# adapterSchematic.net
KiCad netlist of a schematic drawn in EAGLE
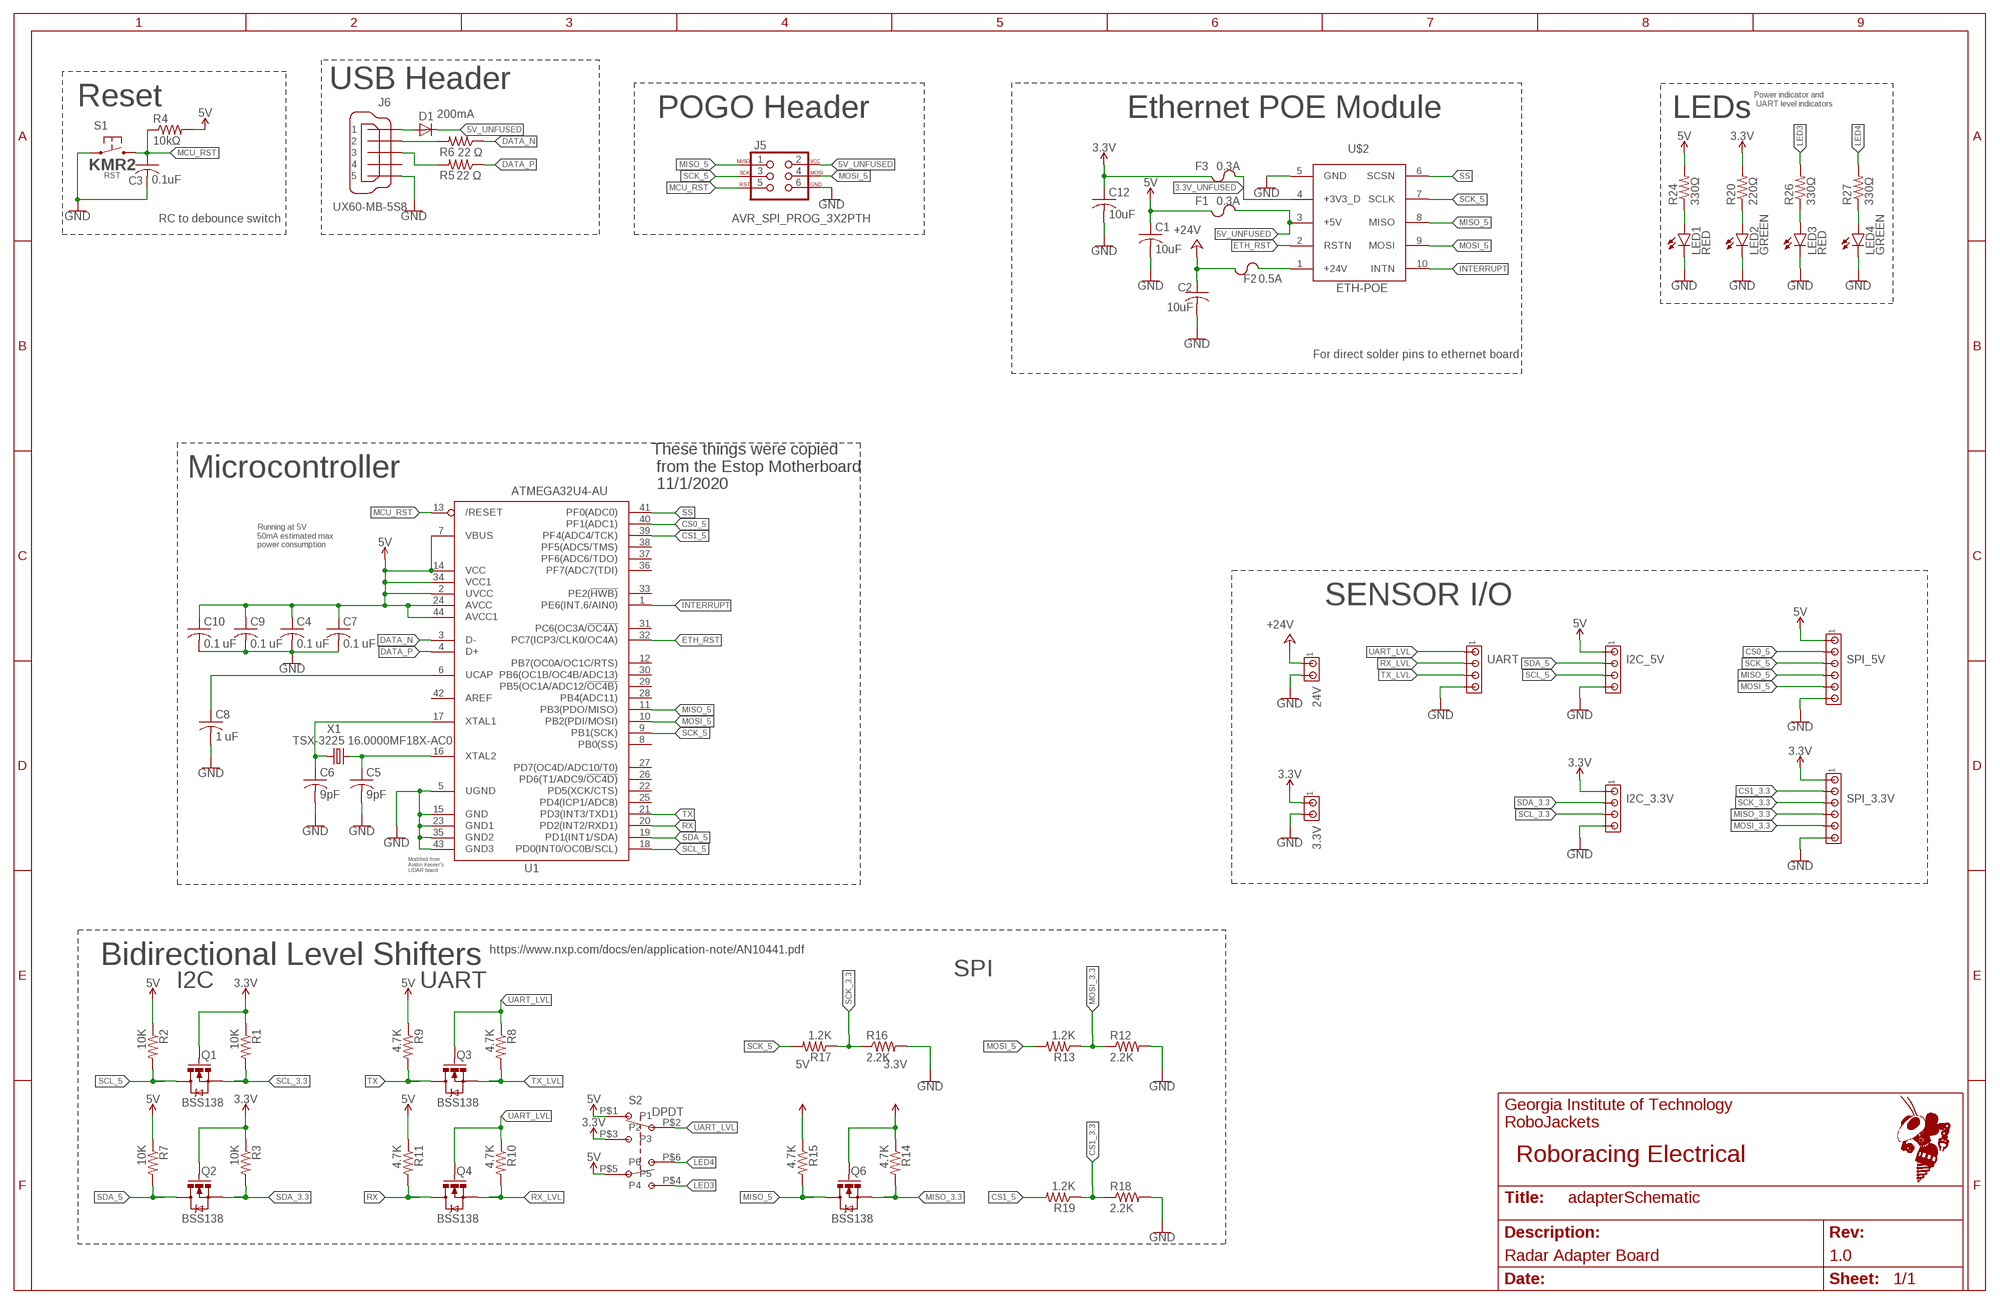
[diagram p0: schematic, sheet 1]

(export (version "E")
  (design (tool "Eeschema 10.0.6"))
  (components
    (comp (ref "3.3V")
      (value "MTA02-100")
      (footprint "eagle-import:10X02MTA")
      (libsource (lib "eagle-import") (part "MTA02-100"))
    )
    (comp (ref "24V")
      (value "MTA02-100")
      (footprint "eagle-import:10X02MTA")
      (libsource (lib "eagle-import") (part "MTA02-100"))
    )
    (comp (ref "C1")
      (value "10uF")
      (footprint "eagle-import:C1206")
      (libsource (lib "eagle-import") (part "C-USC1206"))
    )
    (comp (ref "C2")
      (value "10uF")
      (footprint "eagle-import:C1206")
      (libsource (lib "eagle-import") (part "C-USC1206"))
    )
    (comp (ref "C3")
      (value "0.1uF")
      (footprint "eagle-import:C0603")
      (libsource (lib "eagle-import") (part "C-USC0603"))
    )
    (comp (ref "C4")
      (value "0.1 uF")
      (footprint "eagle-import:C0603")
      (libsource (lib "eagle-import") (part "resistor_348_C-USC0603"))
    )
    (comp (ref "C5")
      (value "9pF")
      (footprint "eagle-import:C0603")
      (libsource (lib "eagle-import") (part "resistor_348_C-USC0603"))
    )
    (comp (ref "C6")
      (value "9pF")
      (footprint "eagle-import:C0603")
      (libsource (lib "eagle-import") (part "resistor_348_C-USC0603"))
    )
    (comp (ref "C7")
      (value "0.1 uF")
      (footprint "eagle-import:C0603")
      (libsource (lib "eagle-import") (part "resistor_348_C-USC0603"))
    )
    (comp (ref "C8")
      (value "1 uF")
      (footprint "eagle-import:C0603")
      (libsource (lib "eagle-import") (part "resistor_348_C-USC0603"))
    )
    (comp (ref "C9")
      (value "0.1 uF")
      (footprint "eagle-import:C0603")
      (libsource (lib "eagle-import") (part "resistor_348_C-USC0603"))
    )
    (comp (ref "C10")
      (value "0.1 uF")
      (footprint "eagle-import:C0603")
      (libsource (lib "eagle-import") (part "resistor_348_C-USC0603"))
    )
    (comp (ref "C12")
      (value "10uF")
      (footprint "eagle-import:C1206")
      (libsource (lib "eagle-import") (part "C-USC1206"))
    )
    (comp (ref "D1")
      (value "200mA")
      (footprint "eagle-import:SOD323-R")
      (libsource (lib "eagle-import") (part "DIODE-SOD323-R"))
    )
    (comp (ref "F1")
      (value "0.3A")
      (footprint "eagle-import:F1206")
      (libsource (lib "eagle-import") (part "CHIP_FUSE1206"))
    )
    (comp (ref "F2")
      (value "0.5A")
      (footprint "eagle-import:F1206")
      (libsource (lib "eagle-import") (part "CHIP_FUSE1206"))
    )
    (comp (ref "F3")
      (value "0.3A")
      (footprint "eagle-import:F1206")
      (libsource (lib "eagle-import") (part "CHIP_FUSE1206"))
    )
    (comp (ref "I2C_3.3V")
      (value "MTA04-100")
      (footprint "eagle-import:10X04MTA")
      (libsource (lib "eagle-import") (part "MTA04-100"))
    )
    (comp (ref "I2C_5V")
      (value "MTA04-100")
      (footprint "eagle-import:10X04MTA")
      (libsource (lib "eagle-import") (part "MTA04-100"))
    )
    (comp (ref "J5")
      (value "AVR_SPI_PROG_3X2PTH")
      (footprint "eagle-import:2X3")
      (libsource (lib "eagle-import") (part "AVR_SPI_PROG_3X2PTH"))
    )
    (comp (ref "J6")
      (value "UX60-MB-5S8")
      (footprint "eagle-import:UX60-MB-5S8")
      (libsource (lib "eagle-import") (part "UX60-MB-5S?8"))
    )
    (comp (ref "LED1")
      (value "RED")
      (footprint "eagle-import:CHIP-LED0603")
      (libsource (lib "eagle-import") (part "LEDCHIP-LED0603"))
    )
    (comp (ref "LED2")
      (value "GREEN")
      (footprint "eagle-import:CHIP-LED0603")
      (libsource (lib "eagle-import") (part "LEDCHIP-LED0603"))
    )
    (comp (ref "LED3")
      (value "RED")
      (footprint "eagle-import:CHIP-LED0603")
      (libsource (lib "eagle-import") (part "LEDCHIP-LED0603"))
    )
    (comp (ref "LED4")
      (value "GREEN")
      (footprint "eagle-import:CHIP-LED0603")
      (libsource (lib "eagle-import") (part "LEDCHIP-LED0603"))
    )
    (comp (ref "Q1")
      (value "BSS138")
      (footprint "eagle-import:SOT23-3")
      (libsource (lib "eagle-import") (part "MOSFET-NCHANNELSMD"))
    )
    (comp (ref "Q2")
      (value "BSS138")
      (footprint "eagle-import:SOT23-3")
      (libsource (lib "eagle-import") (part "MOSFET-NCHANNELSMD"))
    )
    (comp (ref "Q3")
      (value "BSS138")
      (footprint "eagle-import:SOT23-3")
      (libsource (lib "eagle-import") (part "MOSFET-NCHANNELSMD"))
    )
    (comp (ref "Q4")
      (value "BSS138")
      (footprint "eagle-import:SOT23-3")
      (libsource (lib "eagle-import") (part "MOSFET-NCHANNELSMD"))
    )
    (comp (ref "Q6")
      (value "BSS138")
      (footprint "eagle-import:SOT23-3")
      (libsource (lib "eagle-import") (part "MOSFET-NCHANNELSMD"))
    )
    (comp (ref "R1")
      (value "10K")
      (footprint "eagle-import:0603-RES")
      (libsource (lib "eagle-import") (part "RESISTOR0603-RES"))
    )
    (comp (ref "R2")
      (value "10K")
      (footprint "eagle-import:0603-RES")
      (libsource (lib "eagle-import") (part "RESISTOR0603-RES"))
    )
    (comp (ref "R3")
      (value "10K")
      (footprint "eagle-import:0603-RES")
      (libsource (lib "eagle-import") (part "RESISTOR0603-RES"))
    )
    (comp (ref "R4")
      (value "10kΩ")
      (footprint "eagle-import:R0603")
      (libsource (lib "eagle-import") (part "R-US_R0603"))
    )
    (comp (ref "R5")
      (value "22 Ω")
      (footprint "eagle-import:R0603")
      (libsource (lib "eagle-import") (part "R-US_R0603"))
    )
    (comp (ref "R6")
      (value "22 Ω")
      (footprint "eagle-import:R0603")
      (libsource (lib "eagle-import") (part "R-US_R0603"))
    )
    (comp (ref "R7")
      (value "10K")
      (footprint "eagle-import:0603-RES")
      (libsource (lib "eagle-import") (part "RESISTOR0603-RES"))
    )
    (comp (ref "R8")
      (value "4.7K")
      (footprint "eagle-import:0603-RES")
      (libsource (lib "eagle-import") (part "RESISTOR0603-RES"))
    )
    (comp (ref "R9")
      (value "4.7K")
      (footprint "eagle-import:0603-RES")
      (libsource (lib "eagle-import") (part "RESISTOR0603-RES"))
    )
    (comp (ref "R10")
      (value "4.7K")
      (footprint "eagle-import:0603-RES")
      (libsource (lib "eagle-import") (part "RESISTOR0603-RES"))
    )
    (comp (ref "R11")
      (value "4.7K")
      (footprint "eagle-import:0603-RES")
      (libsource (lib "eagle-import") (part "RESISTOR0603-RES"))
    )
    (comp (ref "R12")
      (value "2.2K")
      (footprint "eagle-import:0603-RES")
      (libsource (lib "eagle-import") (part "RESISTOR0603-RES"))
    )
    (comp (ref "R13")
      (value "1.2K")
      (footprint "eagle-import:0603-RES")
      (libsource (lib "eagle-import") (part "RESISTOR0603-RES"))
    )
    (comp (ref "R14")
      (value "4.7K")
      (footprint "eagle-import:0603-RES")
      (libsource (lib "eagle-import") (part "RESISTOR0603-RES"))
    )
    (comp (ref "R15")
      (value "4.7K")
      (footprint "eagle-import:0603-RES")
      (libsource (lib "eagle-import") (part "RESISTOR0603-RES"))
    )
    (comp (ref "R16")
      (value "2.2K")
      (footprint "eagle-import:0603-RES")
      (libsource (lib "eagle-import") (part "RESISTOR0603-RES"))
    )
    (comp (ref "R17")
      (value "1.2K")
      (footprint "eagle-import:0603-RES")
      (libsource (lib "eagle-import") (part "RESISTOR0603-RES"))
    )
    (comp (ref "R18")
      (value "2.2K")
      (footprint "eagle-import:0603-RES")
      (libsource (lib "eagle-import") (part "RESISTOR0603-RES"))
    )
    (comp (ref "R19")
      (value "1.2K")
      (footprint "eagle-import:0603-RES")
      (libsource (lib "eagle-import") (part "RESISTOR0603-RES"))
    )
    (comp (ref "R20")
      (value "220Ω")
      (footprint "eagle-import:R0603")
      (libsource (lib "eagle-import") (part "R-US_R0603"))
    )
    (comp (ref "R24")
      (value "330Ω")
      (footprint "eagle-import:R0603")
      (libsource (lib "eagle-import") (part "R-US_R0603"))
    )
    (comp (ref "R26")
      (value "330Ω")
      (footprint "eagle-import:R0603")
      (libsource (lib "eagle-import") (part "R-US_R0603"))
    )
    (comp (ref "R27")
      (value "330Ω")
      (footprint "eagle-import:R0603")
      (libsource (lib "eagle-import") (part "R-US_R0603"))
    )
    (comp (ref "S1")
      (value "KMR2")
      (footprint "eagle-import:KMR2")
      (fields (field (name "FUNCTION") "Reset") (field (name "FUNCTION_1") "RST"))
      (libsource (lib "eagle-import") (part "KMR2"))
    )
    (comp (ref "SPI_3.3V")
      (value "MTA06-100")
      (footprint "eagle-import:10X06MTA")
      (libsource (lib "eagle-import") (part "MTA06-100"))
    )
    (comp (ref "SPI_5V")
      (value "MTA06-100")
      (footprint "eagle-import:10X06MTA")
      (libsource (lib "eagle-import") (part "MTA06-100"))
    )
    (comp (ref "U$2")
      (value "ETH-POE")
      (footprint "eagle-import:HDRVR10W64P4000X254_2X5_1016X508X254B")
      (libsource (lib "eagle-import") (part "ETH-POE"))
    )
    (comp (ref "U$4")
      (value "DPDT_SLIDE_SWITCH")
      (footprint "eagle-import:DPDT_SLIDE_SWITCH")
      (libsource (lib "eagle-import") (part "DPDT_SLIDE_SWITCH"))
    )
    (comp (ref "U1")
      (value "ATMEGA32U4-AU")
      (footprint "eagle-import:TQFP44")
      (libsource (lib "eagle-import") (part "ATMEGA32U4-AU"))
    )
    (comp (ref "UART")
      (value "MTA04-100")
      (footprint "eagle-import:10X04MTA")
      (libsource (lib "eagle-import") (part "MTA04-100"))
    )
    (comp (ref "X1")
      (value "TSX-3225 16.0000MF18X-AC0")
      (footprint "eagle-import:XTAL-3.2X2.5")
      (libsource (lib "eagle-import") (part "XTAL-3.2X2.5"))
    )
  )
  (nets
    (net (code "1") (name "+24V") (class "Default")
      (node (ref "24V") (pin "1") (pinfunction "1_1") (pintype "passive"))
      (node (ref "C2") (pin "1") (pinfunction "1_1") (pintype "passive"))
      (node (ref "F2") (pin "1") (pinfunction "1_1") (pintype "bidirectional"))
    )
    (net (code "2") (name "3.3V") (class "Default")
      (node (ref "3.3V") (pin "1") (pinfunction "1_1") (pintype "passive"))
      (node (ref "C12") (pin "1") (pinfunction "1_1") (pintype "passive"))
      (node (ref "F3") (pin "1") (pinfunction "1_1") (pintype "bidirectional"))
      (node (ref "I2C_3.3V") (pin "1") (pinfunction "1_1") (pintype "passive"))
      (node (ref "Q1") (pin "1") (pinfunction "G_1") (pintype "passive"))
      (node (ref "Q2") (pin "1") (pinfunction "G_1") (pintype "passive"))
      (node (ref "Q6") (pin "1") (pinfunction "G_1") (pintype "passive"))
      (node (ref "R1") (pin "1") (pinfunction "1_1") (pintype "passive"))
      (node (ref "R14") (pin "1") (pinfunction "1_1") (pintype "passive"))
      (node (ref "R20") (pin "2") (pinfunction "2_2") (pintype "passive"))
      (node (ref "R3") (pin "1") (pinfunction "1_1") (pintype "passive"))
      (node (ref "SPI_3.3V") (pin "1") (pinfunction "1_1") (pintype "passive"))
      (node (ref "U$4") (pin "P$3") (pinfunction "P3_P$3") (pintype "bidirectional"))
    )
    (net (code "3") (name "3.3V_UNFUSED") (class "Default")
      (node (ref "F3") (pin "2") (pinfunction "2_2") (pintype "bidirectional"))
      (node (ref "U$2") (pin "4") (pinfunction "+3V3_D_4") (pintype "bidirectional"))
    )
    (net (code "4") (name "5V") (class "Default")
      (node (ref "C1") (pin "1") (pinfunction "1_1") (pintype "passive"))
      (node (ref "C10") (pin "1") (pinfunction "1_1") (pintype "passive"))
      (node (ref "C4") (pin "1") (pinfunction "1_1") (pintype "passive"))
      (node (ref "C7") (pin "1") (pinfunction "1_1") (pintype "passive"))
      (node (ref "C9") (pin "1") (pinfunction "1_1") (pintype "passive"))
      (node (ref "F1") (pin "1") (pinfunction "1_1") (pintype "bidirectional"))
      (node (ref "I2C_5V") (pin "1") (pinfunction "1_1") (pintype "passive"))
      (node (ref "R11") (pin "1") (pinfunction "1_1") (pintype "passive"))
      (node (ref "R15") (pin "1") (pinfunction "1_1") (pintype "passive"))
      (node (ref "R2") (pin "1") (pinfunction "1_1") (pintype "passive"))
      (node (ref "R24") (pin "2") (pinfunction "2_2") (pintype "passive"))
      (node (ref "R4") (pin "2") (pinfunction "2_2") (pintype "passive"))
      (node (ref "R7") (pin "1") (pinfunction "1_1") (pintype "passive"))
      (node (ref "R9") (pin "1") (pinfunction "1_1") (pintype "passive"))
      (node (ref "SPI_5V") (pin "1") (pinfunction "1_1") (pintype "passive"))
      (node (ref "U$4") (pin "P$1") (pinfunction "P1_P$1") (pintype "bidirectional"))
      (node (ref "U$4") (pin "P$5") (pinfunction "P5_P$5") (pintype "bidirectional"))
      (node (ref "U1") (pin "14") (pinfunction "VCC_14") (pintype "bidirectional"))
      (node (ref "U1") (pin "2") (pinfunction "UVCC_2") (pintype "bidirectional"))
      (node (ref "U1") (pin "24") (pinfunction "AVCC_24") (pintype "bidirectional"))
      (node (ref "U1") (pin "34") (pinfunction "VCC1_34") (pintype "bidirectional"))
      (node (ref "U1") (pin "44") (pinfunction "AVCC1_44") (pintype "bidirectional"))
      (node (ref "U1") (pin "7") (pinfunction "VBUS_7") (pintype "bidirectional"))
    )
    (net (code "5") (name "5V_UNFUSED") (class "Default")
      (node (ref "D1") (pin "C") (pinfunction "C_C") (pintype "passive"))
      (node (ref "F1") (pin "2") (pinfunction "2_2") (pintype "bidirectional"))
      (node (ref "J5") (pin "2") (pinfunction "2_2") (pintype "passive"))
      (node (ref "U$2") (pin "3") (pinfunction "+5V_3") (pintype "bidirectional"))
    )
    (net (code "6") (name "CS0_5") (class "Default")
      (node (ref "SPI_5V") (pin "2") (pinfunction "2_2") (pintype "passive"))
      (node (ref "U1") (pin "40") (pinfunction "PF1(ADC1)_40") (pintype "bidirectional"))
    )
    (net (code "7") (name "CS1_3.3") (class "Default")
      (node (ref "R18") (pin "1") (pinfunction "1_1") (pintype "passive"))
      (node (ref "R19") (pin "1") (pinfunction "1_1") (pintype "passive"))
      (node (ref "SPI_3.3V") (pin "2") (pinfunction "2_2") (pintype "passive"))
    )
    (net (code "8") (name "CS1_5") (class "Default")
      (node (ref "R19") (pin "2") (pinfunction "2_2") (pintype "passive"))
      (node (ref "U1") (pin "39") (pinfunction "PF4(ADC4/TCK)_39") (pintype "bidirectional"))
    )
    (net (code "9") (name "DATA_N") (class "Default")
      (node (ref "R6") (pin "1") (pinfunction "1_1") (pintype "passive"))
      (node (ref "U1") (pin "3") (pinfunction "D-_3") (pintype "bidirectional"))
    )
    (net (code "10") (name "DATA_P") (class "Default")
      (node (ref "R5") (pin "1") (pinfunction "1_1") (pintype "passive"))
      (node (ref "U1") (pin "4") (pinfunction "D+_4") (pintype "bidirectional"))
    )
    (net (code "11") (name "ETH_RST") (class "Default")
      (node (ref "U$2") (pin "2") (pinfunction "RSTN_2") (pintype "bidirectional"))
      (node (ref "U1") (pin "32") (pinfunction "PC7(ICP3/CLK0/OC4A)_32") (pintype "bidirectional"))
    )
    (net (code "12") (name "GND") (class "Default")
      (node (ref "24V") (pin "2") (pinfunction "2_2") (pintype "passive"))
      (node (ref "3.3V") (pin "2") (pinfunction "2_2") (pintype "passive"))
      (node (ref "C1") (pin "2") (pinfunction "2_2") (pintype "passive"))
      (node (ref "C10") (pin "2") (pinfunction "2_2") (pintype "passive"))
      (node (ref "C12") (pin "2") (pinfunction "2_2") (pintype "passive"))
      (node (ref "C2") (pin "2") (pinfunction "2_2") (pintype "passive"))
      (node (ref "C3") (pin "2") (pinfunction "2_2") (pintype "passive"))
      (node (ref "C4") (pin "2") (pinfunction "2_2") (pintype "passive"))
      (node (ref "C5") (pin "2") (pinfunction "2_2") (pintype "passive"))
      (node (ref "C6") (pin "2") (pinfunction "2_2") (pintype "passive"))
      (node (ref "C7") (pin "2") (pinfunction "2_2") (pintype "passive"))
      (node (ref "C8") (pin "2") (pinfunction "2_2") (pintype "passive"))
      (node (ref "C9") (pin "2") (pinfunction "2_2") (pintype "passive"))
      (node (ref "I2C_3.3V") (pin "4") (pinfunction "4_4") (pintype "passive"))
      (node (ref "I2C_5V") (pin "4") (pinfunction "4_4") (pintype "passive"))
      (node (ref "J5") (pin "6") (pinfunction "6_6") (pintype "passive"))
      (node (ref "J6") (pin "5") (pinfunction "5_5") (pintype "passive"))
      (node (ref "LED1") (pin "C") (pinfunction "C_C") (pintype "passive"))
      (node (ref "LED2") (pin "C") (pinfunction "C_C") (pintype "passive"))
      (node (ref "LED3") (pin "C") (pinfunction "C_C") (pintype "passive"))
      (node (ref "LED4") (pin "C") (pinfunction "C_C") (pintype "passive"))
      (node (ref "R12") (pin "2") (pinfunction "2_2") (pintype "passive"))
      (node (ref "R16") (pin "2") (pinfunction "2_2") (pintype "passive"))
      (node (ref "R18") (pin "2") (pinfunction "2_2") (pintype "passive"))
      (node (ref "S1") (pin "1.1") (pinfunction "1_1.1") (pintype "passive"))
      (node (ref "S1") (pin "1.2") (pinfunction "1_1.2") (pintype "passive"))
      (node (ref "SPI_3.3V") (pin "6") (pinfunction "6_6") (pintype "passive"))
      (node (ref "SPI_5V") (pin "6") (pinfunction "6_6") (pintype "passive"))
      (node (ref "U$2") (pin "5") (pinfunction "GND_5") (pintype "bidirectional"))
      (node (ref "U1") (pin "15") (pinfunction "GND_15") (pintype "bidirectional"))
      (node (ref "U1") (pin "23") (pinfunction "GND1_23") (pintype "bidirectional"))
      (node (ref "U1") (pin "35") (pinfunction "GND2_35") (pintype "bidirectional"))
      (node (ref "U1") (pin "43") (pinfunction "GND3_43") (pintype "bidirectional"))
      (node (ref "U1") (pin "5") (pinfunction "UGND_5") (pintype "bidirectional"))
      (node (ref "UART") (pin "4") (pinfunction "4_4") (pintype "passive"))
    )
    (net (code "13") (name "INTERRUPT") (class "Default")
      (node (ref "U$2") (pin "10") (pinfunction "INTN_10") (pintype "bidirectional"))
      (node (ref "U1") (pin "1") (pinfunction "PE6(INT.6/AIN0)_1") (pintype "bidirectional"))
    )
    (net (code "14") (name "LED3") (class "Default")
      (node (ref "R26") (pin "2") (pinfunction "2_2") (pintype "passive"))
      (node (ref "U$4") (pin "P$4") (pinfunction "P4_P$4") (pintype "bidirectional"))
    )
    (net (code "15") (name "LED4") (class "Default")
      (node (ref "R27") (pin "2") (pinfunction "2_2") (pintype "passive"))
      (node (ref "U$4") (pin "P$6") (pinfunction "P6_P$6") (pintype "bidirectional"))
    )
    (net (code "16") (name "MCU_RST") (class "Default")
      (node (ref "C3") (pin "1") (pinfunction "1_1") (pintype "passive"))
      (node (ref "J5") (pin "5") (pinfunction "5_5") (pintype "passive"))
      (node (ref "R4") (pin "1") (pinfunction "1_1") (pintype "passive"))
      (node (ref "S1") (pin "2.1") (pinfunction "2_2.1") (pintype "passive"))
      (node (ref "S1") (pin "2.2") (pinfunction "2_2.2") (pintype "passive"))
      (node (ref "U1") (pin "13") (pinfunction "/RESET_13") (pintype "bidirectional"))
    )
    (net (code "17") (name "MISO_3.3") (class "Default")
      (node (ref "Q6") (pin "2") (pinfunction "S_2") (pintype "passive"))
      (node (ref "R14") (pin "2") (pinfunction "2_2") (pintype "passive"))
      (node (ref "SPI_3.3V") (pin "4") (pinfunction "4_4") (pintype "passive"))
    )
    (net (code "18") (name "MISO_5") (class "Default")
      (node (ref "J5") (pin "1") (pinfunction "1_1") (pintype "passive"))
      (node (ref "Q6") (pin "3") (pinfunction "D_3") (pintype "passive"))
      (node (ref "R15") (pin "2") (pinfunction "2_2") (pintype "passive"))
      (node (ref "SPI_5V") (pin "4") (pinfunction "4_4") (pintype "passive"))
      (node (ref "U$2") (pin "8") (pinfunction "MISO_8") (pintype "bidirectional"))
      (node (ref "U1") (pin "11") (pinfunction "PB3(PDO/MISO)_11") (pintype "bidirectional"))
    )
    (net (code "19") (name "MOSI_3.3") (class "Default")
      (node (ref "R12") (pin "1") (pinfunction "1_1") (pintype "passive"))
      (node (ref "R13") (pin "1") (pinfunction "1_1") (pintype "passive"))
      (node (ref "SPI_3.3V") (pin "5") (pinfunction "5_5") (pintype "passive"))
    )
    (net (code "20") (name "MOSI_5") (class "Default")
      (node (ref "J5") (pin "4") (pinfunction "4_4") (pintype "passive"))
      (node (ref "R13") (pin "2") (pinfunction "2_2") (pintype "passive"))
      (node (ref "SPI_5V") (pin "5") (pinfunction "5_5") (pintype "passive"))
      (node (ref "U$2") (pin "9") (pinfunction "MOSI_9") (pintype "bidirectional"))
      (node (ref "U1") (pin "10") (pinfunction "PB2(PDI/MOSI)_10") (pintype "bidirectional"))
    )
    (net (code "21") (name "Net-(D1-PadA)") (class "Default")
      (node (ref "D1") (pin "A") (pinfunction "A_A") (pintype "passive"))
      (node (ref "J6") (pin "1") (pinfunction "1_1") (pintype "passive"))
    )
    (net (code "22") (name "Net-(J6-Pad2)") (class "Default")
      (node (ref "J6") (pin "2") (pinfunction "2_2") (pintype "passive"))
      (node (ref "R6") (pin "2") (pinfunction "2_2") (pintype "passive"))
    )
    (net (code "23") (name "Net-(J6-Pad3)") (class "Default")
      (node (ref "J6") (pin "3") (pinfunction "3_3") (pintype "passive"))
      (node (ref "R5") (pin "2") (pinfunction "2_2") (pintype "passive"))
    )
    (net (code "24") (name "Net-(LED1-PadA)") (class "Default")
      (node (ref "LED1") (pin "A") (pinfunction "A_A") (pintype "passive"))
      (node (ref "R24") (pin "1") (pinfunction "1_1") (pintype "passive"))
    )
    (net (code "25") (name "Net-(LED2-PadA)") (class "Default")
      (node (ref "LED2") (pin "A") (pinfunction "A_A") (pintype "passive"))
      (node (ref "R20") (pin "1") (pinfunction "1_1") (pintype "passive"))
    )
    (net (code "26") (name "Net-(LED3-PadA)") (class "Default")
      (node (ref "LED3") (pin "A") (pinfunction "A_A") (pintype "passive"))
      (node (ref "R26") (pin "1") (pinfunction "1_1") (pintype "passive"))
    )
    (net (code "27") (name "Net-(LED4-PadA)") (class "Default")
      (node (ref "LED4") (pin "A") (pinfunction "A_A") (pintype "passive"))
      (node (ref "R27") (pin "1") (pinfunction "1_1") (pintype "passive"))
    )
    (net (code "28") (name "Net-(U$2-+24V)") (class "Default")
      (node (ref "F2") (pin "2") (pinfunction "2_2") (pintype "bidirectional"))
      (node (ref "U$2") (pin "1") (pinfunction "+24V_1") (pintype "bidirectional"))
    )
    (net (code "29") (name "Net-(U1-UCAP)") (class "Default")
      (node (ref "C8") (pin "1") (pinfunction "1_1") (pintype "passive"))
      (node (ref "U1") (pin "6") (pinfunction "UCAP_6") (pintype "bidirectional"))
    )
    (net (code "30") (name "Net-(U1-XTAL1)") (class "Default")
      (node (ref "C6") (pin "1") (pinfunction "1_1") (pintype "passive"))
      (node (ref "U1") (pin "17") (pinfunction "XTAL1_17") (pintype "bidirectional"))
      (node (ref "X1") (pin "1") (pinfunction "1_1") (pintype "passive"))
    )
    (net (code "31") (name "Net-(U1-XTAL2)") (class "Default")
      (node (ref "C5") (pin "1") (pinfunction "1_1") (pintype "passive"))
      (node (ref "U1") (pin "16") (pinfunction "XTAL2_16") (pintype "bidirectional"))
      (node (ref "X1") (pin "3") (pinfunction "2_3") (pintype "passive"))
    )
    (net (code "32") (name "RX") (class "Default")
      (node (ref "Q4") (pin "3") (pinfunction "D_3") (pintype "passive"))
      (node (ref "R11") (pin "2") (pinfunction "2_2") (pintype "passive"))
      (node (ref "U1") (pin "20") (pinfunction "PD2(INT2/RXD1)_20") (pintype "bidirectional"))
    )
    (net (code "33") (name "RX_LVL") (class "Default")
      (node (ref "Q4") (pin "2") (pinfunction "S_2") (pintype "passive"))
      (node (ref "R10") (pin "2") (pinfunction "2_2") (pintype "passive"))
      (node (ref "UART") (pin "2") (pinfunction "2_2") (pintype "passive"))
    )
    (net (code "34") (name "SCK_3.3") (class "Default")
      (node (ref "R16") (pin "1") (pinfunction "1_1") (pintype "passive"))
      (node (ref "R17") (pin "1") (pinfunction "1_1") (pintype "passive"))
      (node (ref "SPI_3.3V") (pin "3") (pinfunction "3_3") (pintype "passive"))
    )
    (net (code "35") (name "SCK_5") (class "Default")
      (node (ref "J5") (pin "3") (pinfunction "3_3") (pintype "passive"))
      (node (ref "R17") (pin "2") (pinfunction "2_2") (pintype "passive"))
      (node (ref "SPI_5V") (pin "3") (pinfunction "3_3") (pintype "passive"))
      (node (ref "U$2") (pin "7") (pinfunction "SCLK_7") (pintype "bidirectional"))
      (node (ref "U1") (pin "9") (pinfunction "PB1(SCK)_9") (pintype "bidirectional"))
    )
    (net (code "36") (name "SCL_3.3") (class "Default")
      (node (ref "I2C_3.3V") (pin "3") (pinfunction "3_3") (pintype "passive"))
      (node (ref "Q1") (pin "2") (pinfunction "S_2") (pintype "passive"))
      (node (ref "R1") (pin "2") (pinfunction "2_2") (pintype "passive"))
    )
    (net (code "37") (name "SCL_5") (class "Default")
      (node (ref "I2C_5V") (pin "3") (pinfunction "3_3") (pintype "passive"))
      (node (ref "Q1") (pin "3") (pinfunction "D_3") (pintype "passive"))
      (node (ref "R2") (pin "2") (pinfunction "2_2") (pintype "passive"))
      (node (ref "U1") (pin "18") (pinfunction "PD0(INT0/OC0B/SCL)_18") (pintype "bidirectional"))
    )
    (net (code "38") (name "SDA_3.3") (class "Default")
      (node (ref "I2C_3.3V") (pin "2") (pinfunction "2_2") (pintype "passive"))
      (node (ref "Q2") (pin "2") (pinfunction "S_2") (pintype "passive"))
      (node (ref "R3") (pin "2") (pinfunction "2_2") (pintype "passive"))
    )
    (net (code "39") (name "SDA_5") (class "Default")
      (node (ref "I2C_5V") (pin "2") (pinfunction "2_2") (pintype "passive"))
      (node (ref "Q2") (pin "3") (pinfunction "D_3") (pintype "passive"))
      (node (ref "R7") (pin "2") (pinfunction "2_2") (pintype "passive"))
      (node (ref "U1") (pin "19") (pinfunction "PD1(INT1/SDA)_19") (pintype "bidirectional"))
    )
    (net (code "40") (name "SS") (class "Default")
      (node (ref "U$2") (pin "6") (pinfunction "SCSN_6") (pintype "bidirectional"))
      (node (ref "U1") (pin "41") (pinfunction "PF0(ADC0)_41") (pintype "bidirectional"))
    )
    (net (code "41") (name "TX") (class "Default")
      (node (ref "Q3") (pin "3") (pinfunction "D_3") (pintype "passive"))
      (node (ref "R9") (pin "2") (pinfunction "2_2") (pintype "passive"))
      (node (ref "U1") (pin "21") (pinfunction "PD3(INT3/TXD1)_21") (pintype "bidirectional"))
    )
    (net (code "42") (name "TX_LVL") (class "Default")
      (node (ref "Q3") (pin "2") (pinfunction "S_2") (pintype "passive"))
      (node (ref "R8") (pin "2") (pinfunction "2_2") (pintype "passive"))
      (node (ref "UART") (pin "3") (pinfunction "3_3") (pintype "passive"))
    )
    (net (code "43") (name "UART_LVL") (class "Default")
      (node (ref "Q3") (pin "1") (pinfunction "G_1") (pintype "passive"))
      (node (ref "Q4") (pin "1") (pinfunction "G_1") (pintype "passive"))
      (node (ref "R10") (pin "1") (pinfunction "1_1") (pintype "passive"))
      (node (ref "R8") (pin "1") (pinfunction "1_1") (pintype "passive"))
      (node (ref "U$4") (pin "P$2") (pinfunction "P2_P$2") (pintype "bidirectional"))
      (node (ref "UART") (pin "1") (pinfunction "1_1") (pintype "passive"))
    )
    (net (code "44") (name "unconnected-(J6-Pad4)") (class "Default")
      (node (ref "J6") (pin "4") (pinfunction "4_4") (pintype "passive"))
    )
    (net (code "45") (name "unconnected-(U1-AREF-Pad42)") (class "Default")
      (node (ref "U1") (pin "42") (pinfunction "AREF_42") (pintype "bidirectional"))
    )
    (net (code "46") (name "unconnected-(U1-PB0(SS)-Pad8)") (class "Default")
      (node (ref "U1") (pin "8") (pinfunction "PB0(SS)_8") (pintype "bidirectional"))
    )
    (net (code "47") (name "unconnected-(U1-PB4(ADC11)-Pad28)") (class "Default")
      (node (ref "U1") (pin "28") (pinfunction "PB4(ADC11)_28") (pintype "bidirectional"))
    )
    (net (code "48") (name "unconnected-(U1-PB5(OC1A{slash}ADC12{slash}~{OC4B})-Pad29)") (class "Default")
      (node (ref "U1") (pin "29") (pinfunction "PB5(OC1A/ADC12/~{OC4B})_29") (pintype "bidirectional"))
    )
    (net (code "49") (name "unconnected-(U1-PB6(OC1B{slash}OC4B{slash}ADC13)-Pad30)") (class "Default")
      (node (ref "U1") (pin "30") (pinfunction "PB6(OC1B/OC4B/ADC13)_30") (pintype "bidirectional"))
    )
    (net (code "50") (name "unconnected-(U1-PB7(OC0A{slash}OC1C{slash}RTS)-Pad12)") (class "Default")
      (node (ref "U1") (pin "12") (pinfunction "PB7(OC0A/OC1C/RTS)_12") (pintype "bidirectional"))
    )
    (net (code "51") (name "unconnected-(U1-PC6(OC3A{slash}~{OC4A})-Pad31)") (class "Default")
      (node (ref "U1") (pin "31") (pinfunction "PC6(OC3A/~{OC4A})_31") (pintype "bidirectional"))
    )
    (net (code "52") (name "unconnected-(U1-PD4(ICP1{slash}ADC8)-Pad25)") (class "Default")
      (node (ref "U1") (pin "25") (pinfunction "PD4(ICP1/ADC8)_25") (pintype "bidirectional"))
    )
    (net (code "53") (name "unconnected-(U1-PD5(XCK{slash}CTS)-Pad22)") (class "Default")
      (node (ref "U1") (pin "22") (pinfunction "PD5(XCK/CTS)_22") (pintype "bidirectional"))
    )
    (net (code "54") (name "unconnected-(U1-PD6(T1{slash}ADC9{slash}~{OC4D})-Pad26)") (class "Default")
      (node (ref "U1") (pin "26") (pinfunction "PD6(T1/ADC9/~{OC4D})_26") (pintype "bidirectional"))
    )
    (net (code "55") (name "unconnected-(U1-PD7(OC4D{slash}ADC10{slash}T0)-Pad27)") (class "Default")
      (node (ref "U1") (pin "27") (pinfunction "PD7(OC4D/ADC10/T0)_27") (pintype "bidirectional"))
    )
    (net (code "56") (name "unconnected-(U1-PE2(~{HWB})-Pad33)") (class "Default")
      (node (ref "U1") (pin "33") (pinfunction "PE2(~{HWB})_33") (pintype "bidirectional"))
    )
    (net (code "57") (name "unconnected-(U1-PF5(ADC5{slash}TMS)-Pad38)") (class "Default")
      (node (ref "U1") (pin "38") (pinfunction "PF5(ADC5/TMS)_38") (pintype "bidirectional"))
    )
    (net (code "58") (name "unconnected-(U1-PF6(ADC6{slash}TDO)-Pad37)") (class "Default")
      (node (ref "U1") (pin "37") (pinfunction "PF6(ADC6/TDO)_37") (pintype "bidirectional"))
    )
    (net (code "59") (name "unconnected-(U1-PF7(ADC7(TDI)-Pad36)") (class "Default")
      (node (ref "U1") (pin "36") (pinfunction "PF7(ADC7(TDI)_36") (pintype "bidirectional"))
    )
  )
)
